# Simple_Boost_JST_to_1V8.net
KiCad netlist of a schematic drawn in EAGLE
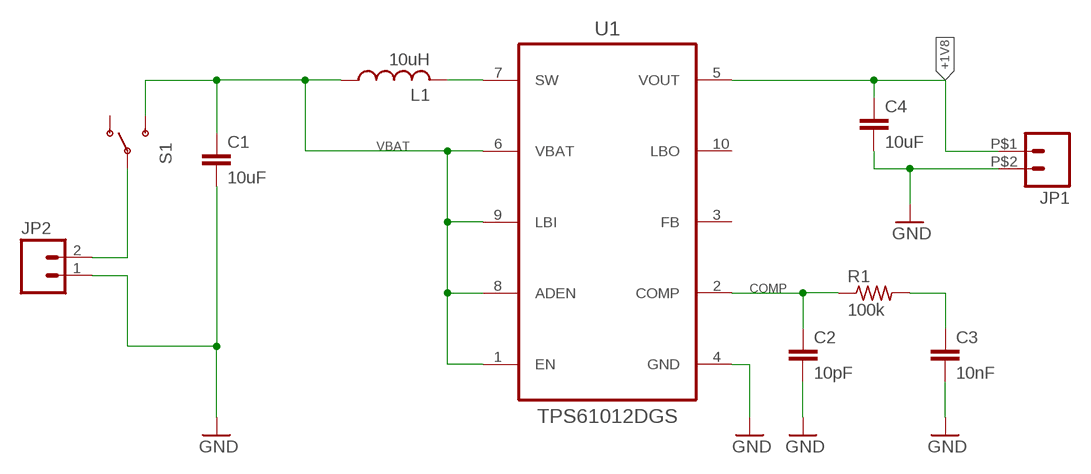
[diagram p0: schematic, sheet 1]

(export (version "E")
  (design (tool "Eeschema 10.0.6"))
  (components
    (comp (ref "C1")
      (value "10uF")
      (footprint "eagle-import:C1812")
      (libsource (lib "eagle-import") (part "C-EUC1812"))
    )
    (comp (ref "C2")
      (value "10pF")
      (footprint "eagle-import:C0805")
      (libsource (lib "eagle-import") (part "C-EUC0805"))
    )
    (comp (ref "C3")
      (value "10nF")
      (footprint "eagle-import:C0805")
      (libsource (lib "eagle-import") (part "C-EUC0805"))
    )
    (comp (ref "C4")
      (value "10uF")
      (footprint "eagle-import:C1812")
      (libsource (lib "eagle-import") (part "C-EUC1812"))
    )
    (comp (ref "JP1")
      (value "M02TE-282834-2")
      (footprint "eagle-import:1X02_282834-2")
      (libsource (lib "eagle-import") (part "M02TE-282834-2"))
    )
    (comp (ref "JP2")
      (value "M02JST-PTH-2")
      (footprint "eagle-import:JST-2-PTH")
      (libsource (lib "eagle-import") (part "M02JST-PTH-2"))
    )
    (comp (ref "L1")
      (value "10uH")
      (footprint "eagle-import:CDRH6D38")
      (libsource (lib "eagle-import") (part "SUMIDA_POWER_INDUCTOR6"))
    )
    (comp (ref "R1")
      (value "100k")
      (footprint "eagle-import:R0805")
      (libsource (lib "eagle-import") (part "R-US_R0805"))
    )
    (comp (ref "S1")
      (value "SWITCH-SPDTPTH")
      (footprint "eagle-import:SWITCH-SPDT")
      (libsource (lib "eagle-import") (part "SWITCH-SPDTPTH"))
    )
    (comp (ref "U1")
      (value "TPS61012DGS")
      (footprint "eagle-import:SOP50P490X110-10N")
      (fields (field (name "VOLTAGE") "1.8"))
      (libsource (lib "eagle-import") (part "TPS6101DGS2"))
    )
  )
  (nets
    (net (code "1") (name "+1V8") (class "Default")
      (node (ref "C4") (pin "1") (pinfunction "1_1") (pintype "passive"))
      (node (ref "JP1") (pin "P$1") (pinfunction "1_P$1") (pintype "passive"))
      (node (ref "U1") (pin "5") (pinfunction "VOUT_5") (pintype "output"))
    )
    (net (code "2") (name "/COMP") (class "Default")
      (node (ref "C2") (pin "1") (pinfunction "1_1") (pintype "passive"))
      (node (ref "R1") (pin "1") (pinfunction "1_1") (pintype "passive"))
      (node (ref "U1") (pin "2") (pinfunction "COMP_2") (pintype "input"))
    )
    (net (code "3") (name "/VBAT") (class "Default")
      (node (ref "C1") (pin "1") (pinfunction "1_1") (pintype "passive"))
      (node (ref "L1") (pin "P$1") (pinfunction "1_P$1") (pintype "passive"))
      (node (ref "S1") (pin "3") (pinfunction "S_3") (pintype "passive"))
      (node (ref "U1") (pin "1") (pinfunction "EN_1") (pintype "input"))
      (node (ref "U1") (pin "6") (pinfunction "VBAT_6") (pintype "power_in"))
      (node (ref "U1") (pin "8") (pinfunction "ADEN_8") (pintype "input"))
      (node (ref "U1") (pin "9") (pinfunction "LBI_9") (pintype "input"))
    )
    (net (code "4") (name "GND") (class "Default")
      (node (ref "C1") (pin "2") (pinfunction "2_2") (pintype "passive"))
      (node (ref "C2") (pin "2") (pinfunction "2_2") (pintype "passive"))
      (node (ref "C3") (pin "2") (pinfunction "2_2") (pintype "passive"))
      (node (ref "C4") (pin "2") (pinfunction "2_2") (pintype "passive"))
      (node (ref "JP1") (pin "P$2") (pinfunction "2_P$2") (pintype "passive"))
      (node (ref "JP2") (pin "1") (pinfunction "1_1") (pintype "passive"))
      (node (ref "U1") (pin "4") (pinfunction "GND_4") (pintype "passive"))
    )
    (net (code "5") (name "Net-(C3-Pad1)") (class "Default")
      (node (ref "C3") (pin "1") (pinfunction "1_1") (pintype "passive"))
      (node (ref "R1") (pin "2") (pinfunction "2_2") (pintype "passive"))
    )
    (net (code "6") (name "Net-(L1-2)") (class "Default")
      (node (ref "L1") (pin "P$2") (pinfunction "2_P$2") (pintype "passive"))
      (node (ref "U1") (pin "7") (pinfunction "SW_7") (pintype "input"))
    )
    (net (code "7") (name "Net-(S1-P)") (class "Default")
      (node (ref "JP2") (pin "2") (pinfunction "2_2") (pintype "passive"))
      (node (ref "S1") (pin "2") (pinfunction "P_2") (pintype "passive"))
    )
    (net (code "8") (name "unconnected-(S1-O-Pad1)") (class "Default")
      (node (ref "S1") (pin "1") (pinfunction "O_1") (pintype "passive"))
    )
    (net (code "9") (name "unconnected-(U1-FB-Pad3)") (class "Default")
      (node (ref "U1") (pin "3") (pinfunction "FB_3") (pintype "input"))
    )
    (net (code "10") (name "unconnected-(U1-LBO-Pad10)") (class "Default")
      (node (ref "U1") (pin "10") (pinfunction "LBO_10") (pintype "output"))
    )
  )
)
